# DasAltimeter_V0_1.net
KiCad netlist of a schematic drawn in EAGLE
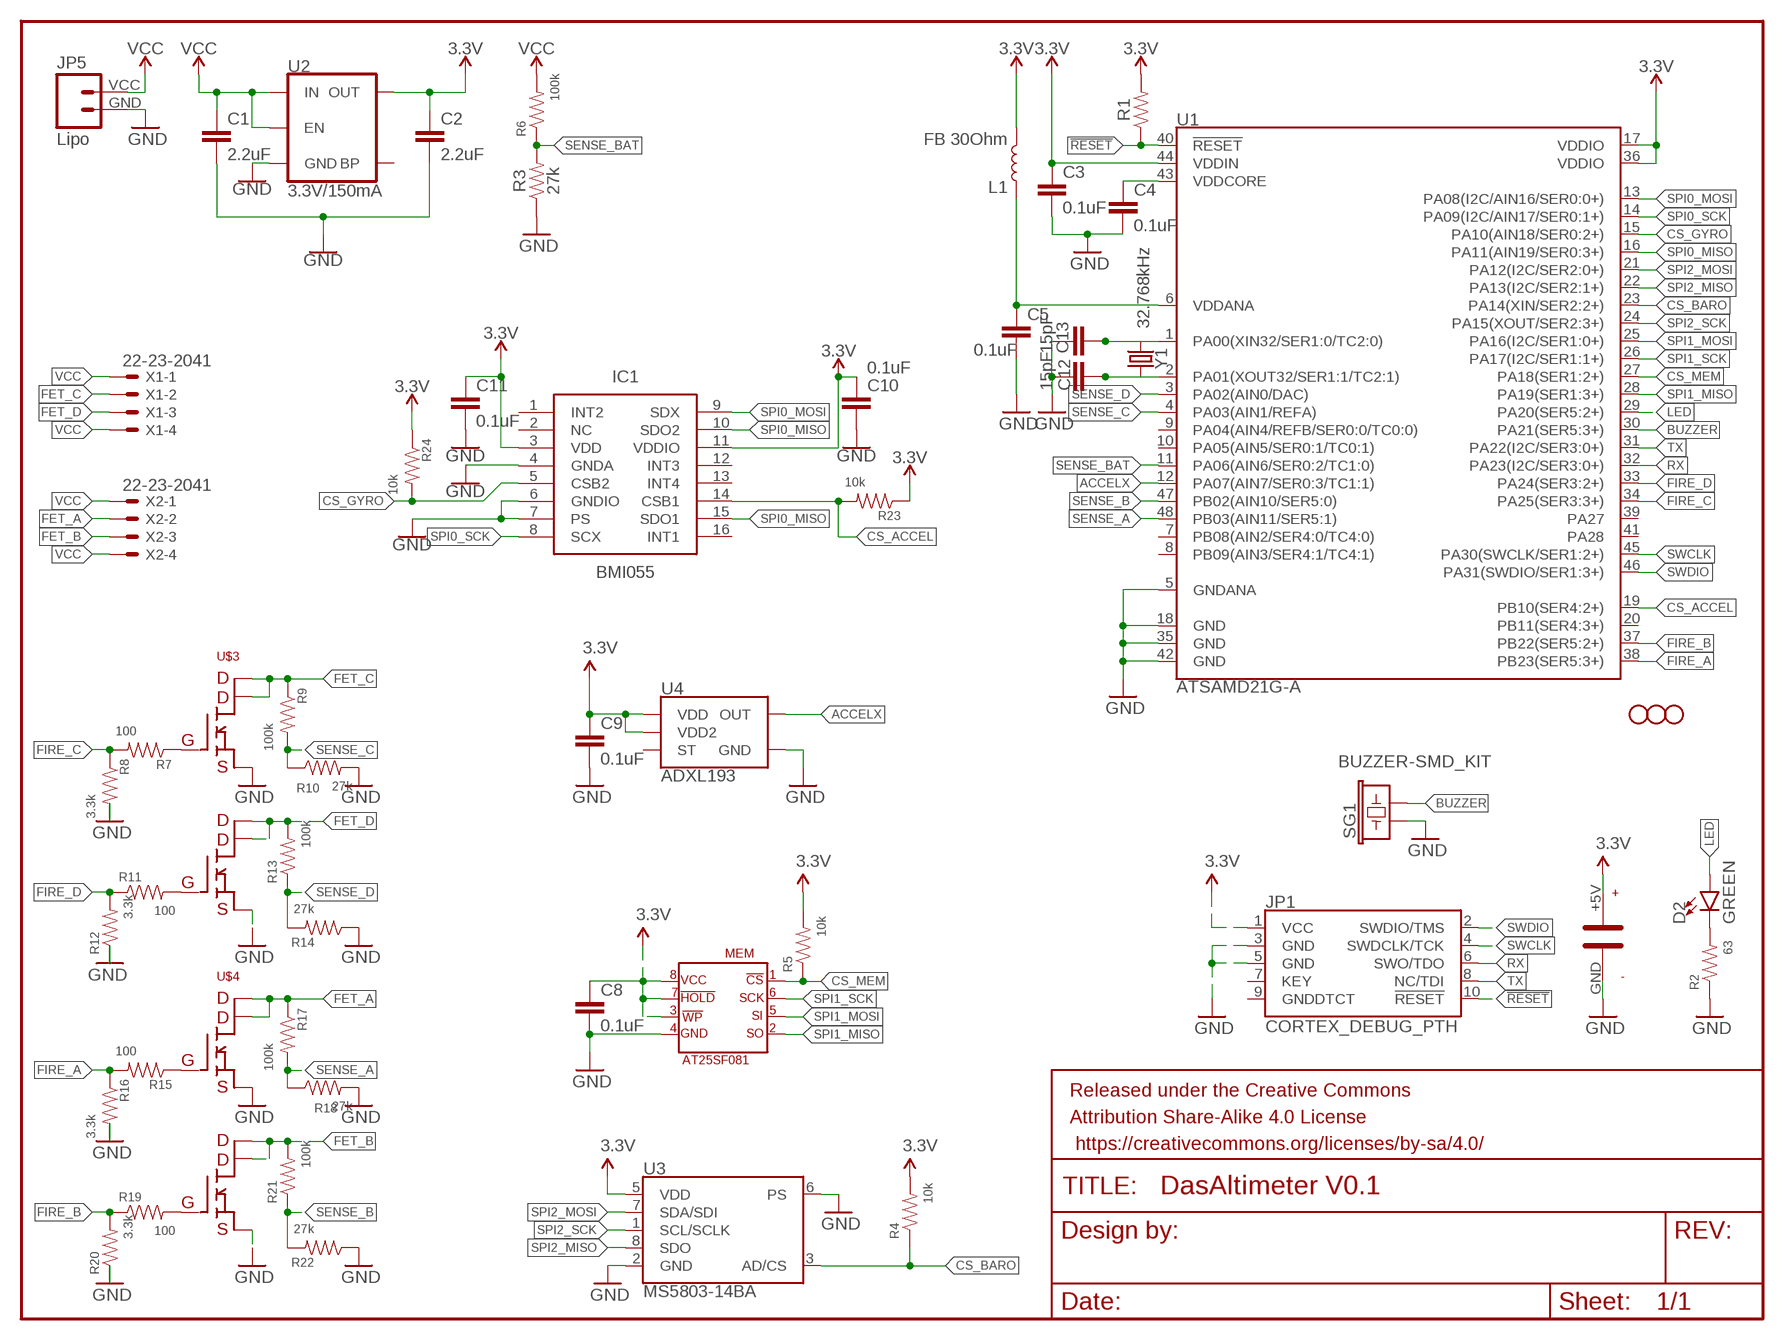
[diagram p0: schematic, sheet 1]

(export (version "E")
  (design (tool "Eeschema 10.0.6"))
  (components
    (comp (ref "C1")
      (value "2.2uF")
      (footprint "eagle-import:0603")
      (libsource (lib "eagle-import") (part "2.2UF-0603-10V-20%"))
    )
    (comp (ref "C2")
      (value "2.2uF")
      (footprint "eagle-import:0603")
      (libsource (lib "eagle-import") (part "2.2UF-0603-10V-20%"))
    )
    (comp (ref "C3")
      (value "0.1uF")
      (footprint "eagle-import:0402")
      (libsource (lib "eagle-import") (part "0.1UF-0402-16V-10%"))
    )
    (comp (ref "C4")
      (value "0.1uF")
      (footprint "eagle-import:0402")
      (libsource (lib "eagle-import") (part "0.1UF-0402-16V-10%"))
    )
    (comp (ref "C5")
      (value "0.1uF")
      (footprint "eagle-import:0402")
      (libsource (lib "eagle-import") (part "0.1UF-0402-16V-10%"))
    )
    (comp (ref "C8")
      (value "0.1uF")
      (footprint "eagle-import:0402")
      (libsource (lib "eagle-import") (part "0.1UF-0402-16V-10%"))
    )
    (comp (ref "C9")
      (value "0.1uF")
      (footprint "eagle-import:0402")
      (libsource (lib "eagle-import") (part "0.1UF-0402-16V-10%"))
    )
    (comp (ref "C10")
      (value "0.1uF")
      (footprint "eagle-import:0402")
      (libsource (lib "eagle-import") (part "0.1UF-0402-16V-10%"))
    )
    (comp (ref "C11")
      (value "0.1uF")
      (footprint "eagle-import:0402")
      (libsource (lib "eagle-import") (part "0.1UF-0402-16V-10%"))
    )
    (comp (ref "C12")
      (value "15pF")
      (footprint "eagle-import:0402")
      (libsource (lib "eagle-import") (part "15PF-0402-50V-5%"))
    )
    (comp (ref "C13")
      (value "15pF")
      (footprint "eagle-import:0402")
      (libsource (lib "eagle-import") (part "15PF-0402-50V-5%"))
    )
    (comp (ref "D2")
      (value "GREEN")
      (footprint "eagle-import:LED-1206")
      (libsource (lib "eagle-import") (part "LED-GREEN1206"))
    )
    (comp (ref "FRAME1")
      (value "FRAME-LETTERNO_PACKAGE")
      (footprint "eagle-import:DUMMY")
      (fields (field (name "DESIGNER") "Nobody"))
      (libsource (lib "eagle-import") (part "FRAME-LETTERNO_PACKAGE"))
    )
    (comp (ref "H1")
      (value "STAND-OFFTIGHT")
      (footprint "eagle-import:STAND-OFF-TIGHT")
      (libsource (lib "eagle-import") (part "STAND-OFFTIGHT"))
    )
    (comp (ref "H2")
      (value "STAND-OFFTIGHT")
      (footprint "eagle-import:STAND-OFF-TIGHT")
      (libsource (lib "eagle-import") (part "STAND-OFFTIGHT"))
    )
    (comp (ref "H3")
      (value "STAND-OFFTIGHT")
      (footprint "eagle-import:STAND-OFF-TIGHT")
      (libsource (lib "eagle-import") (part "STAND-OFFTIGHT"))
    )
    (comp (ref "IC1")
      (value "BMI055")
      (footprint "eagle-import:BMI055")
      (libsource (lib "eagle-import") (part "BMI055"))
    )
    (comp (ref "JP1")
      (value "CORTEX_DEBUG_PTH")
      (footprint "eagle-import:2X5-PTH-1.27MM")
      (libsource (lib "eagle-import") (part "CORTEX_DEBUG_PTH"))
    )
    (comp (ref "JP5")
      (value "Lipo")
      (footprint "eagle-import:JST-2-SMD-VERT")
      (libsource (lib "eagle-import") (part "M024UCON-15767"))
    )
    (comp (ref "L1")
      (value "FB 30Ohm")
      (footprint "eagle-import:0603")
      (libsource (lib "eagle-import") (part "INDUCTOR-0603-33NH"))
    )
    (comp (ref "MEM")
      (value "AT25SF081")
      (footprint "eagle-import:AT25SF081")
      (libsource (lib "eagle-import") (part "AT25SF081"))
    )
    (comp (ref "R1")
      (value "RESISTOR0402")
      (footprint "eagle-import:0402")
      (libsource (lib "eagle-import") (part "RESISTOR0402"))
    )
    (comp (ref "R2")
      (value "63")
      (footprint "eagle-import:0402")
      (libsource (lib "eagle-import") (part "RESISTOR0402"))
    )
    (comp (ref "R3")
      (value "27k")
      (footprint "eagle-import:0402")
      (libsource (lib "eagle-import") (part "RESISTOR0402"))
    )
    (comp (ref "R4")
      (value "10k")
      (footprint "eagle-import:0402")
      (libsource (lib "eagle-import") (part "RESISTOR0402"))
    )
    (comp (ref "R5")
      (value "10k")
      (footprint "eagle-import:0402")
      (libsource (lib "eagle-import") (part "RESISTOR0402"))
    )
    (comp (ref "R6")
      (value "100k")
      (footprint "eagle-import:0402")
      (libsource (lib "eagle-import") (part "RESISTOR0402"))
    )
    (comp (ref "R7")
      (value "100")
      (footprint "eagle-import:0402")
      (libsource (lib "eagle-import") (part "RESISTOR0402"))
    )
    (comp (ref "R8")
      (value "3.3k")
      (footprint "eagle-import:0402")
      (libsource (lib "eagle-import") (part "RESISTOR0402"))
    )
    (comp (ref "R9")
      (value "100k")
      (footprint "eagle-import:0402")
      (libsource (lib "eagle-import") (part "RESISTOR0402"))
    )
    (comp (ref "R10")
      (value "27k")
      (footprint "eagle-import:0402")
      (libsource (lib "eagle-import") (part "RESISTOR0402"))
    )
    (comp (ref "R11")
      (value "100")
      (footprint "eagle-import:0402")
      (libsource (lib "eagle-import") (part "RESISTOR0402"))
    )
    (comp (ref "R12")
      (value "3.3k")
      (footprint "eagle-import:0402")
      (libsource (lib "eagle-import") (part "RESISTOR0402"))
    )
    (comp (ref "R13")
      (value "100k")
      (footprint "eagle-import:0402")
      (libsource (lib "eagle-import") (part "RESISTOR0402"))
    )
    (comp (ref "R14")
      (value "27k")
      (footprint "eagle-import:0402")
      (libsource (lib "eagle-import") (part "RESISTOR0402"))
    )
    (comp (ref "R15")
      (value "100")
      (footprint "eagle-import:0402")
      (libsource (lib "eagle-import") (part "RESISTOR0402"))
    )
    (comp (ref "R16")
      (value "3.3k")
      (footprint "eagle-import:0402")
      (libsource (lib "eagle-import") (part "RESISTOR0402"))
    )
    (comp (ref "R17")
      (value "100k")
      (footprint "eagle-import:0402")
      (libsource (lib "eagle-import") (part "RESISTOR0402"))
    )
    (comp (ref "R18")
      (value "27k")
      (footprint "eagle-import:0402")
      (libsource (lib "eagle-import") (part "RESISTOR0402"))
    )
    (comp (ref "R19")
      (value "100")
      (footprint "eagle-import:0402")
      (libsource (lib "eagle-import") (part "RESISTOR0402"))
    )
    (comp (ref "R20")
      (value "3.3k")
      (footprint "eagle-import:0402")
      (libsource (lib "eagle-import") (part "RESISTOR0402"))
    )
    (comp (ref "R21")
      (value "100k")
      (footprint "eagle-import:0402")
      (libsource (lib "eagle-import") (part "RESISTOR0402"))
    )
    (comp (ref "R22")
      (value "27k")
      (footprint "eagle-import:0402")
      (libsource (lib "eagle-import") (part "RESISTOR0402"))
    )
    (comp (ref "R23")
      (value "10k")
      (footprint "eagle-import:0402")
      (libsource (lib "eagle-import") (part "RESISTOR0402"))
    )
    (comp (ref "R24")
      (value "10k")
      (footprint "eagle-import:0402")
      (libsource (lib "eagle-import") (part "RESISTOR0402"))
    )
    (comp (ref "SG1")
      (value "BUZZER-SMD_KIT")
      (footprint "eagle-import:BUZZER-CCV-KIT")
      (libsource (lib "eagle-import") (part "BUZZER-SMD_KIT"))
    )
    (comp (ref "U$1")
      (value "PB-5R0H104-R")
      (footprint "eagle-import:PB-5R0H104-R")
      (libsource (lib "eagle-import") (part "PB-5R0H104-R"))
    )
    (comp (ref "U$3")
      (value "SI7232DN")
      (footprint "eagle-import:SI7232DN")
      (libsource (lib "eagle-import") (part "SI7232DN"))
    )
    (comp (ref "U$4")
      (value "SI7232DN")
      (footprint "eagle-import:SI7232DN")
      (libsource (lib "eagle-import") (part "SI7232DN"))
    )
    (comp (ref "U1")
      (value "ATSAMD21G-A")
      (footprint "eagle-import:TQFP-48")
      (libsource (lib "eagle-import") (part "ATSAMD21G-A"))
    )
    (comp (ref "U2")
      (value "3.3V/150mA")
      (footprint "eagle-import:SOT23-5")
      (libsource (lib "eagle-import") (part "V_REG_MIC52053.3V"))
    )
    (comp (ref "U3")
      (value "MS5803-14BA")
      (footprint "eagle-import:MS5803")
      (libsource (lib "eagle-import") (part "MS5803-14BA"))
    )
    (comp (ref "U4")
      (value "ADXL193")
      (footprint "eagle-import:LCC-8")
      (libsource (lib "eagle-import") (part "ADXL193"))
    )
    (comp (ref "X1")
      (value "22-23-2041")
      (footprint "eagle-import:22-23-2041")
      (fields (field (name "MF") "MOLEX"))
      (libsource (lib "eagle-import") (part "22-23-2041"))
    )
    (comp (ref "X2")
      (value "22-23-2041")
      (footprint "eagle-import:22-23-2041")
      (fields (field (name "MF") "MOLEX"))
      (libsource (lib "eagle-import") (part "22-23-2041"))
    )
    (comp (ref "Y1")
      (value "32.768kHz")
      (footprint "eagle-import:CRYSTAL-SMD-3.2X1.5MM")
      (libsource (lib "eagle-import") (part "CRYSTAL-32.768KHZSMD-3.2X1.5"))
    )
  )
  (nets
    (net (code "1") (name "/~{RESET}") (class "Default")
      (node (ref "JP1") (pin "10") (pinfunction "~{RESET}_10") (pintype "bidirectional"))
      (node (ref "R1") (pin "1") (pinfunction "1_1") (pintype "passive"))
      (node (ref "U1") (pin "40") (pinfunction "~{RESET}_40") (pintype "bidirectional"))
    )
    (net (code "2") (name "3.3V") (class "Default")
      (node (ref "C10") (pin "1") (pinfunction "1_1") (pintype "passive"))
      (node (ref "C11") (pin "1") (pinfunction "1_1") (pintype "passive"))
      (node (ref "C2") (pin "1") (pinfunction "1_1") (pintype "passive"))
      (node (ref "C3") (pin "1") (pinfunction "1_1") (pintype "passive"))
      (node (ref "C8") (pin "1") (pinfunction "1_1") (pintype "passive"))
      (node (ref "C9") (pin "1") (pinfunction "1_1") (pintype "passive"))
      (node (ref "IC1") (pin "11") (pinfunction "VDDIO_11") (pintype "passive"))
      (node (ref "IC1") (pin "3") (pinfunction "VDD_3") (pintype "passive"))
      (node (ref "JP1") (pin "1") (pinfunction "VCC_1") (pintype "bidirectional"))
      (node (ref "L1") (pin "2") (pinfunction "2_2") (pintype "passive"))
      (node (ref "MEM") (pin "!HOLD") (pinfunction "~{HOLD}_!HOLD") (pintype "bidirectional"))
      (node (ref "MEM") (pin "!WP") (pinfunction "~{WP}_!WP") (pintype "bidirectional"))
      (node (ref "MEM") (pin "VCC") (pinfunction "VCC_VCC") (pintype "bidirectional"))
      (node (ref "R1") (pin "2") (pinfunction "2_2") (pintype "passive"))
      (node (ref "R23") (pin "1") (pinfunction "1_1") (pintype "passive"))
      (node (ref "R24") (pin "1") (pinfunction "1_1") (pintype "passive"))
      (node (ref "R4") (pin "2") (pinfunction "2_2") (pintype "passive"))
      (node (ref "R5") (pin "2") (pinfunction "2_2") (pintype "passive"))
      (node (ref "U$1") (pin "+5V") (pinfunction "+5V_+5V") (pintype "bidirectional"))
      (node (ref "U1") (pin "17") (pinfunction "VDDIO_17") (pintype "bidirectional"))
      (node (ref "U1") (pin "36") (pinfunction "VDDIO_36") (pintype "bidirectional"))
      (node (ref "U1") (pin "44") (pinfunction "VDDIN_44") (pintype "bidirectional"))
      (node (ref "U2") (pin "5") (pinfunction "OUT_5") (pintype "passive"))
      (node (ref "U3") (pin "5") (pinfunction "VDD_5") (pintype "bidirectional"))
      (node (ref "U4") (pin "P$7") (pinfunction "VDD_P$7") (pintype "bidirectional"))
      (node (ref "U4") (pin "P$8") (pinfunction "VDD2_P$8") (pintype "bidirectional"))
    )
    (net (code "3") (name "ACCELX") (class "Default")
      (node (ref "U1") (pin "12") (pinfunction "PA07(AIN7/SER0:3/TC1:1)_12") (pintype "bidirectional"))
      (node (ref "U4") (pin "P$6") (pinfunction "OUT_P$6") (pintype "bidirectional"))
    )
    (net (code "4") (name "BUZZER") (class "Default")
      (node (ref "SG1") (pin "-") (pinfunction "2_-") (pintype "passive"))
      (node (ref "U1") (pin "30") (pinfunction "PA21(SER5:3+)_30") (pintype "bidirectional"))
    )
    (net (code "5") (name "CS_ACCEL") (class "Default")
      (node (ref "IC1") (pin "14") (pinfunction "CSB1_14") (pintype "passive"))
      (node (ref "R23") (pin "2") (pinfunction "2_2") (pintype "passive"))
      (node (ref "U1") (pin "19") (pinfunction "PB10(SER4:2+)_19") (pintype "bidirectional"))
    )
    (net (code "6") (name "CS_BARO") (class "Default")
      (node (ref "R4") (pin "1") (pinfunction "1_1") (pintype "passive"))
      (node (ref "U1") (pin "23") (pinfunction "PA14(XIN/SER2:2+)_23") (pintype "bidirectional"))
      (node (ref "U3") (pin "3") (pinfunction "AD/CS_3") (pintype "bidirectional"))
    )
    (net (code "7") (name "CS_GYRO") (class "Default")
      (node (ref "IC1") (pin "5") (pinfunction "CSB2_5") (pintype "passive"))
      (node (ref "R24") (pin "2") (pinfunction "2_2") (pintype "passive"))
      (node (ref "U1") (pin "15") (pinfunction "PA10(AIN18/SER0:2+)_15") (pintype "bidirectional"))
    )
    (net (code "8") (name "CS_MEM") (class "Default")
      (node (ref "MEM") (pin "!CS") (pinfunction "~{CS}_!CS") (pintype "bidirectional"))
      (node (ref "R5") (pin "1") (pinfunction "1_1") (pintype "passive"))
      (node (ref "U1") (pin "27") (pinfunction "PA18(SER1:2+)_27") (pintype "bidirectional"))
    )
    (net (code "9") (name "FET_A") (class "Default")
      (node (ref "R17") (pin "1") (pinfunction "1_1") (pintype "passive"))
      (node (ref "U$4") (pin "7") (pinfunction "PIN7_7") (pintype "bidirectional"))
      (node (ref "U$4") (pin "8") (pinfunction "PIN8_8") (pintype "bidirectional"))
      (node (ref "U$4") (pin "9") (pinfunction "PIN8_9") (pintype "bidirectional"))
      (node (ref "X2") (pin "2") (pinfunction "S_2") (pintype "passive"))
    )
    (net (code "10") (name "FET_B") (class "Default")
      (node (ref "R21") (pin "2") (pinfunction "2_2") (pintype "passive"))
      (node (ref "U$4") (pin "10") (pinfunction "PIN5_10") (pintype "bidirectional"))
      (node (ref "U$4") (pin "5") (pinfunction "PIN5_5") (pintype "bidirectional"))
      (node (ref "U$4") (pin "6") (pinfunction "PIN6_6") (pintype "bidirectional"))
      (node (ref "X2") (pin "3") (pinfunction "S_3") (pintype "passive"))
    )
    (net (code "11") (name "FET_C") (class "Default")
      (node (ref "R9") (pin "1") (pinfunction "1_1") (pintype "passive"))
      (node (ref "U$3") (pin "7") (pinfunction "PIN7_7") (pintype "bidirectional"))
      (node (ref "U$3") (pin "8") (pinfunction "PIN8_8") (pintype "bidirectional"))
      (node (ref "U$3") (pin "9") (pinfunction "PIN8_9") (pintype "bidirectional"))
      (node (ref "X1") (pin "2") (pinfunction "S_2") (pintype "passive"))
    )
    (net (code "12") (name "FET_D") (class "Default")
      (node (ref "R13") (pin "2") (pinfunction "2_2") (pintype "passive"))
      (node (ref "U$3") (pin "10") (pinfunction "PIN5_10") (pintype "bidirectional"))
      (node (ref "U$3") (pin "5") (pinfunction "PIN5_5") (pintype "bidirectional"))
      (node (ref "U$3") (pin "6") (pinfunction "PIN6_6") (pintype "bidirectional"))
      (node (ref "X1") (pin "3") (pinfunction "S_3") (pintype "passive"))
    )
    (net (code "13") (name "FIRE_A") (class "Default")
      (node (ref "R15") (pin "2") (pinfunction "2_2") (pintype "passive"))
      (node (ref "R16") (pin "1") (pinfunction "1_1") (pintype "passive"))
      (node (ref "U1") (pin "38") (pinfunction "PB23(SER5:3+)_38") (pintype "bidirectional"))
    )
    (net (code "14") (name "FIRE_B") (class "Default")
      (node (ref "R19") (pin "1") (pinfunction "1_1") (pintype "passive"))
      (node (ref "R20") (pin "2") (pinfunction "2_2") (pintype "passive"))
      (node (ref "U1") (pin "37") (pinfunction "PB22(SER5:2+)_37") (pintype "bidirectional"))
    )
    (net (code "15") (name "FIRE_C") (class "Default")
      (node (ref "R7") (pin "2") (pinfunction "2_2") (pintype "passive"))
      (node (ref "R8") (pin "1") (pinfunction "1_1") (pintype "passive"))
      (node (ref "U1") (pin "34") (pinfunction "PA25(SER3:3+)_34") (pintype "bidirectional"))
    )
    (net (code "16") (name "FIRE_D") (class "Default")
      (node (ref "R11") (pin "1") (pinfunction "1_1") (pintype "passive"))
      (node (ref "R12") (pin "2") (pinfunction "2_2") (pintype "passive"))
      (node (ref "U1") (pin "33") (pinfunction "PA24(SER3:2+)_33") (pintype "bidirectional"))
    )
    (net (code "17") (name "GND") (class "Default")
      (node (ref "C1") (pin "2") (pinfunction "2_2") (pintype "passive"))
      (node (ref "C10") (pin "2") (pinfunction "2_2") (pintype "passive"))
      (node (ref "C11") (pin "2") (pinfunction "2_2") (pintype "passive"))
      (node (ref "C12") (pin "1") (pinfunction "1_1") (pintype "passive"))
      (node (ref "C13") (pin "1") (pinfunction "1_1") (pintype "passive"))
      (node (ref "C2") (pin "2") (pinfunction "2_2") (pintype "passive"))
      (node (ref "C3") (pin "2") (pinfunction "2_2") (pintype "passive"))
      (node (ref "C4") (pin "2") (pinfunction "2_2") (pintype "passive"))
      (node (ref "C5") (pin "2") (pinfunction "2_2") (pintype "passive"))
      (node (ref "C8") (pin "2") (pinfunction "2_2") (pintype "passive"))
      (node (ref "C9") (pin "2") (pinfunction "2_2") (pintype "passive"))
      (node (ref "IC1") (pin "4") (pinfunction "GNDA_4") (pintype "passive"))
      (node (ref "IC1") (pin "6") (pinfunction "GNDIO_6") (pintype "passive"))
      (node (ref "IC1") (pin "7") (pinfunction "PS_7") (pintype "passive"))
      (node (ref "JP1") (pin "3") (pinfunction "GND_3") (pintype "bidirectional"))
      (node (ref "JP1") (pin "5") (pinfunction "GND_5") (pintype "bidirectional"))
      (node (ref "JP5") (pin "GND") (pinfunction "1_GND") (pintype "passive"))
      (node (ref "MEM") (pin "GND") (pinfunction "GND_GND") (pintype "bidirectional"))
      (node (ref "R10") (pin "2") (pinfunction "2_2") (pintype "passive"))
      (node (ref "R12") (pin "1") (pinfunction "1_1") (pintype "passive"))
      (node (ref "R14") (pin "1") (pinfunction "1_1") (pintype "passive"))
      (node (ref "R16") (pin "2") (pinfunction "2_2") (pintype "passive"))
      (node (ref "R18") (pin "2") (pinfunction "2_2") (pintype "passive"))
      (node (ref "R2") (pin "1") (pinfunction "1_1") (pintype "passive"))
      (node (ref "R20") (pin "1") (pinfunction "1_1") (pintype "passive"))
      (node (ref "R22") (pin "1") (pinfunction "1_1") (pintype "passive"))
      (node (ref "R3") (pin "1") (pinfunction "1_1") (pintype "passive"))
      (node (ref "R8") (pin "2") (pinfunction "2_2") (pintype "passive"))
      (node (ref "SG1") (pin "+") (pinfunction "1_+") (pintype "passive"))
      (node (ref "U$1") (pin "GND") (pinfunction "GND_GND") (pintype "bidirectional"))
      (node (ref "U$3") (pin "1") (pinfunction "PIN1_1") (pintype "bidirectional"))
      (node (ref "U$3") (pin "3") (pinfunction "PIN3_3") (pintype "bidirectional"))
      (node (ref "U$4") (pin "1") (pinfunction "PIN1_1") (pintype "bidirectional"))
      (node (ref "U$4") (pin "3") (pinfunction "PIN3_3") (pintype "bidirectional"))
      (node (ref "U1") (pin "18") (pinfunction "GND_18") (pintype "bidirectional"))
      (node (ref "U1") (pin "35") (pinfunction "GND_35") (pintype "bidirectional"))
      (node (ref "U1") (pin "42") (pinfunction "GND_42") (pintype "bidirectional"))
      (node (ref "U1") (pin "5") (pinfunction "GNDANA_5") (pintype "bidirectional"))
      (node (ref "U2") (pin "2") (pinfunction "GND_2") (pintype "input"))
      (node (ref "U3") (pin "2") (pinfunction "GND_2") (pintype "bidirectional"))
      (node (ref "U3") (pin "6") (pinfunction "PS_6") (pintype "bidirectional"))
      (node (ref "U4") (pin "P$3") (pinfunction "GND_P$3") (pintype "bidirectional"))
    )
    (net (code "18") (name "LED") (class "Default")
      (node (ref "D2") (pin "A") (pinfunction "A_A") (pintype "passive"))
      (node (ref "U1") (pin "29") (pinfunction "PA20(SER5:2+)_29") (pintype "bidirectional"))
    )
    (net (code "19") (name "Net-(D2-PadC)") (class "Default")
      (node (ref "D2") (pin "C") (pinfunction "C_C") (pintype "passive"))
      (node (ref "R2") (pin "2") (pinfunction "2_2") (pintype "passive"))
    )
    (net (code "20") (name "Net-(U$3-PIN2)") (class "Default")
      (node (ref "R7") (pin "1") (pinfunction "1_1") (pintype "passive"))
      (node (ref "U$3") (pin "2") (pinfunction "PIN2_2") (pintype "bidirectional"))
    )
    (net (code "21") (name "Net-(U$3-PIN4)") (class "Default")
      (node (ref "R11") (pin "2") (pinfunction "2_2") (pintype "passive"))
      (node (ref "U$3") (pin "4") (pinfunction "PIN4_4") (pintype "bidirectional"))
    )
    (net (code "22") (name "Net-(U$4-PIN2)") (class "Default")
      (node (ref "R15") (pin "1") (pinfunction "1_1") (pintype "passive"))
      (node (ref "U$4") (pin "2") (pinfunction "PIN2_2") (pintype "bidirectional"))
    )
    (net (code "23") (name "Net-(U$4-PIN4)") (class "Default")
      (node (ref "R19") (pin "2") (pinfunction "2_2") (pintype "passive"))
      (node (ref "U$4") (pin "4") (pinfunction "PIN4_4") (pintype "bidirectional"))
    )
    (net (code "24") (name "Net-(U1-PA00(XIN32{slash}SER1:0{slash}TC2:0))") (class "Default")
      (node (ref "C13") (pin "2") (pinfunction "2_2") (pintype "passive"))
      (node (ref "U1") (pin "1") (pinfunction "PA00(XIN32/SER1:0/TC2:0)_1") (pintype "bidirectional"))
      (node (ref "Y1") (pin "P$2") (pinfunction "2_P$2") (pintype "passive"))
    )
    (net (code "25") (name "Net-(U1-PA01(XOUT32{slash}SER1:1{slash}TC2:1))") (class "Default")
      (node (ref "C12") (pin "2") (pinfunction "2_2") (pintype "passive"))
      (node (ref "U1") (pin "2") (pinfunction "PA01(XOUT32/SER1:1/TC2:1)_2") (pintype "bidirectional"))
      (node (ref "Y1") (pin "P$1") (pinfunction "1_P$1") (pintype "passive"))
    )
    (net (code "26") (name "Net-(U1-VDDANA)") (class "Default")
      (node (ref "C5") (pin "1") (pinfunction "1_1") (pintype "passive"))
      (node (ref "L1") (pin "1") (pinfunction "1_1") (pintype "passive"))
      (node (ref "U1") (pin "6") (pinfunction "VDDANA_6") (pintype "bidirectional"))
    )
    (net (code "27") (name "Net-(U1-VDDCORE)") (class "Default")
      (node (ref "C4") (pin "1") (pinfunction "1_1") (pintype "passive"))
      (node (ref "U1") (pin "43") (pinfunction "VDDCORE_43") (pintype "bidirectional"))
    )
    (net (code "28") (name "RX") (class "Default")
      (node (ref "JP1") (pin "6") (pinfunction "SWO/TDO_6") (pintype "bidirectional"))
      (node (ref "U1") (pin "32") (pinfunction "PA23(I2C/SER3:0+)_32") (pintype "bidirectional"))
    )
    (net (code "29") (name "SENSE_A") (class "Default")
      (node (ref "R17") (pin "2") (pinfunction "2_2") (pintype "passive"))
      (node (ref "R18") (pin "1") (pinfunction "1_1") (pintype "passive"))
      (node (ref "U1") (pin "48") (pinfunction "PB03(AIN11/SER5:1)_48") (pintype "bidirectional"))
    )
    (net (code "30") (name "SENSE_B") (class "Default")
      (node (ref "R21") (pin "1") (pinfunction "1_1") (pintype "passive"))
      (node (ref "R22") (pin "2") (pinfunction "2_2") (pintype "passive"))
      (node (ref "U1") (pin "47") (pinfunction "PB02(AIN10/SER5:0)_47") (pintype "bidirectional"))
    )
    (net (code "31") (name "SENSE_BAT") (class "Default")
      (node (ref "R3") (pin "2") (pinfunction "2_2") (pintype "passive"))
      (node (ref "R6") (pin "1") (pinfunction "1_1") (pintype "passive"))
      (node (ref "U1") (pin "11") (pinfunction "PA06(AIN6/SER0:2/TC1:0)_11") (pintype "bidirectional"))
    )
    (net (code "32") (name "SENSE_C") (class "Default")
      (node (ref "R10") (pin "1") (pinfunction "1_1") (pintype "passive"))
      (node (ref "R9") (pin "2") (pinfunction "2_2") (pintype "passive"))
      (node (ref "U1") (pin "4") (pinfunction "PA03(AIN1/REFA)_4") (pintype "bidirectional"))
    )
    (net (code "33") (name "SENSE_D") (class "Default")
      (node (ref "R13") (pin "1") (pinfunction "1_1") (pintype "passive"))
      (node (ref "R14") (pin "2") (pinfunction "2_2") (pintype "passive"))
      (node (ref "U1") (pin "3") (pinfunction "PA02(AIN0/DAC)_3") (pintype "bidirectional"))
    )
    (net (code "34") (name "SPI0_MISO") (class "Default")
      (node (ref "IC1") (pin "10") (pinfunction "SDO2_10") (pintype "passive"))
      (node (ref "IC1") (pin "15") (pinfunction "SDO1_15") (pintype "passive"))
      (node (ref "U1") (pin "16") (pinfunction "PA11(AIN19/SER0:3+)_16") (pintype "bidirectional"))
    )
    (net (code "35") (name "SPI0_MOSI") (class "Default")
      (node (ref "IC1") (pin "9") (pinfunction "SDX_9") (pintype "passive"))
      (node (ref "U1") (pin "13") (pinfunction "PA08(I2C/AIN16/SER0:0+)_13") (pintype "bidirectional"))
    )
    (net (code "36") (name "SPI0_SCK") (class "Default")
      (node (ref "IC1") (pin "8") (pinfunction "SCX_8") (pintype "passive"))
      (node (ref "U1") (pin "14") (pinfunction "PA09(I2C/AIN17/SER0:1+)_14") (pintype "bidirectional"))
    )
    (net (code "37") (name "SPI1_MISO") (class "Default")
      (node (ref "MEM") (pin "SO") (pinfunction "SO_SO") (pintype "bidirectional"))
      (node (ref "U1") (pin "28") (pinfunction "PA19(SER1:3+)_28") (pintype "bidirectional"))
    )
    (net (code "38") (name "SPI1_MOSI") (class "Default")
      (node (ref "MEM") (pin "SI") (pinfunction "SI_SI") (pintype "bidirectional"))
      (node (ref "U1") (pin "25") (pinfunction "PA16(I2C/SER1:0+)_25") (pintype "bidirectional"))
    )
    (net (code "39") (name "SPI1_SCK") (class "Default")
      (node (ref "MEM") (pin "SCK") (pinfunction "SCK_SCK") (pintype "bidirectional"))
      (node (ref "U1") (pin "26") (pinfunction "PA17(I2C/SER1:1+)_26") (pintype "bidirectional"))
    )
    (net (code "40") (name "SPI2_MISO") (class "Default")
      (node (ref "U1") (pin "22") (pinfunction "PA13(I2C/SER2:1+)_22") (pintype "bidirectional"))
      (node (ref "U3") (pin "8") (pinfunction "SDO_8") (pintype "bidirectional"))
    )
    (net (code "41") (name "SPI2_MOSI") (class "Default")
      (node (ref "U1") (pin "21") (pinfunction "PA12(I2C/SER2:0+)_21") (pintype "bidirectional"))
      (node (ref "U3") (pin "7") (pinfunction "SDA/SDI_7") (pintype "bidirectional"))
    )
    (net (code "42") (name "SPI2_SCK") (class "Default")
      (node (ref "U1") (pin "24") (pinfunction "PA15(XOUT/SER2:3+)_24") (pintype "bidirectional"))
      (node (ref "U3") (pin "1") (pinfunction "SCL/SCLK_1") (pintype "bidirectional"))
    )
    (net (code "43") (name "SWCLK") (class "Default")
      (node (ref "JP1") (pin "4") (pinfunction "SWDCLK/TCK_4") (pintype "bidirectional"))
      (node (ref "U1") (pin "45") (pinfunction "PA30(SWCLK/SER1:2+)_45") (pintype "bidirectional"))
    )
    (net (code "44") (name "SWDIO") (class "Default")
      (node (ref "JP1") (pin "2") (pinfunction "SWDIO/TMS_2") (pintype "bidirectional"))
      (node (ref "U1") (pin "46") (pinfunction "PA31(SWDIO/SER1:3+)_46") (pintype "bidirectional"))
    )
    (net (code "45") (name "TX") (class "Default")
      (node (ref "JP1") (pin "8") (pinfunction "NC/TDI_8") (pintype "bidirectional"))
      (node (ref "U1") (pin "31") (pinfunction "PA22(I2C/SER3:0+)_31") (pintype "bidirectional"))
    )
    (net (code "46") (name "VCC") (class "Default")
      (node (ref "C1") (pin "1") (pinfunction "1_1") (pintype "passive"))
      (node (ref "JP5") (pin "VCC") (pinfunction "2_VCC") (pintype "passive"))
      (node (ref "R6") (pin "2") (pinfunction "2_2") (pintype "passive"))
      (node (ref "U2") (pin "1") (pinfunction "IN_1") (pintype "input"))
      (node (ref "U2") (pin "3") (pinfunction "EN_3") (pintype "input"))
      (node (ref "X1") (pin "1") (pinfunction "S_1") (pintype "passive"))
      (node (ref "X1") (pin "4") (pinfunction "S_4") (pintype "passive"))
      (node (ref "X2") (pin "1") (pinfunction "S_1") (pintype "passive"))
      (node (ref "X2") (pin "4") (pinfunction "S_4") (pintype "passive"))
    )
    (net (code "47") (name "unconnected-(IC1-INT1-Pad16)") (class "Default")
      (node (ref "IC1") (pin "16") (pinfunction "INT1_16") (pintype "passive"))
    )
    (net (code "48") (name "unconnected-(IC1-INT2-Pad1)") (class "Default")
      (node (ref "IC1") (pin "1") (pinfunction "INT2_1") (pintype "passive"))
    )
    (net (code "49") (name "unconnected-(IC1-INT3-Pad12)") (class "Default")
      (node (ref "IC1") (pin "12") (pinfunction "INT3_12") (pintype "passive"))
    )
    (net (code "50") (name "unconnected-(IC1-INT4-Pad13)") (class "Default")
      (node (ref "IC1") (pin "13") (pinfunction "INT4_13") (pintype "passive"))
    )
    (net (code "51") (name "unconnected-(IC1-NC-Pad2)") (class "Default")
      (node (ref "IC1") (pin "2") (pinfunction "NC_2") (pintype "no_connect"))
    )
    (net (code "52") (name "unconnected-(JP1-GNDDTCT-Pad9)") (class "Default")
      (node (ref "JP1") (pin "9") (pinfunction "GNDDTCT_9") (pintype "bidirectional"))
    )
    (net (code "53") (name "unconnected-(JP1-KEY-Pad7)") (class "Default")
      (node (ref "JP1") (pin "7") (pinfunction "KEY_7") (pintype "bidirectional"))
    )
    (net (code "54") (name "unconnected-(U1-PA04(AIN4{slash}REFB{slash}SER0:0{slash}TC0:0)-Pad9)") (class "Default")
      (node (ref "U1") (pin "9") (pinfunction "PA04(AIN4/REFB/SER0:0/TC0:0)_9") (pintype "bidirectional"))
    )
    (net (code "55") (name "unconnected-(U1-PA05(AIN5{slash}SER0:1{slash}TC0:1)-Pad10)") (class "Default")
      (node (ref "U1") (pin "10") (pinfunction "PA05(AIN5/SER0:1/TC0:1)_10") (pintype "bidirectional"))
    )
    (net (code "56") (name "unconnected-(U1-PA27-Pad39)") (class "Default")
      (node (ref "U1") (pin "39") (pinfunction "PA27_39") (pintype "bidirectional"))
    )
    (net (code "57") (name "unconnected-(U1-PA28-Pad41)") (class "Default")
      (node (ref "U1") (pin "41") (pinfunction "PA28_41") (pintype "bidirectional"))
    )
    (net (code "58") (name "unconnected-(U1-PB08(AIN2{slash}SER4:0{slash}TC4:0)-Pad7)") (class "Default")
      (node (ref "U1") (pin "7") (pinfunction "PB08(AIN2/SER4:0/TC4:0)_7") (pintype "bidirectional"))
    )
    (net (code "59") (name "unconnected-(U1-PB09(AIN3{slash}SER4:1{slash}TC4:1)-Pad8)") (class "Default")
      (node (ref "U1") (pin "8") (pinfunction "PB09(AIN3/SER4:1/TC4:1)_8") (pintype "bidirectional"))
    )
    (net (code "60") (name "unconnected-(U1-PB11(SER4:3+)-Pad20)") (class "Default")
      (node (ref "U1") (pin "20") (pinfunction "PB11(SER4:3+)_20") (pintype "bidirectional"))
    )
    (net (code "61") (name "unconnected-(U2-BP-Pad4)") (class "Default")
      (node (ref "U2") (pin "4") (pinfunction "BP_4") (pintype "input"))
    )
    (net (code "62") (name "unconnected-(U4-ST-PadP$4)") (class "Default")
      (node (ref "U4") (pin "P$4") (pinfunction "ST_P$4") (pintype "bidirectional"))
    )
  )
)
